# USF-IEEE-CS.net
KiCad netlist of a schematic drawn in Altium Designer
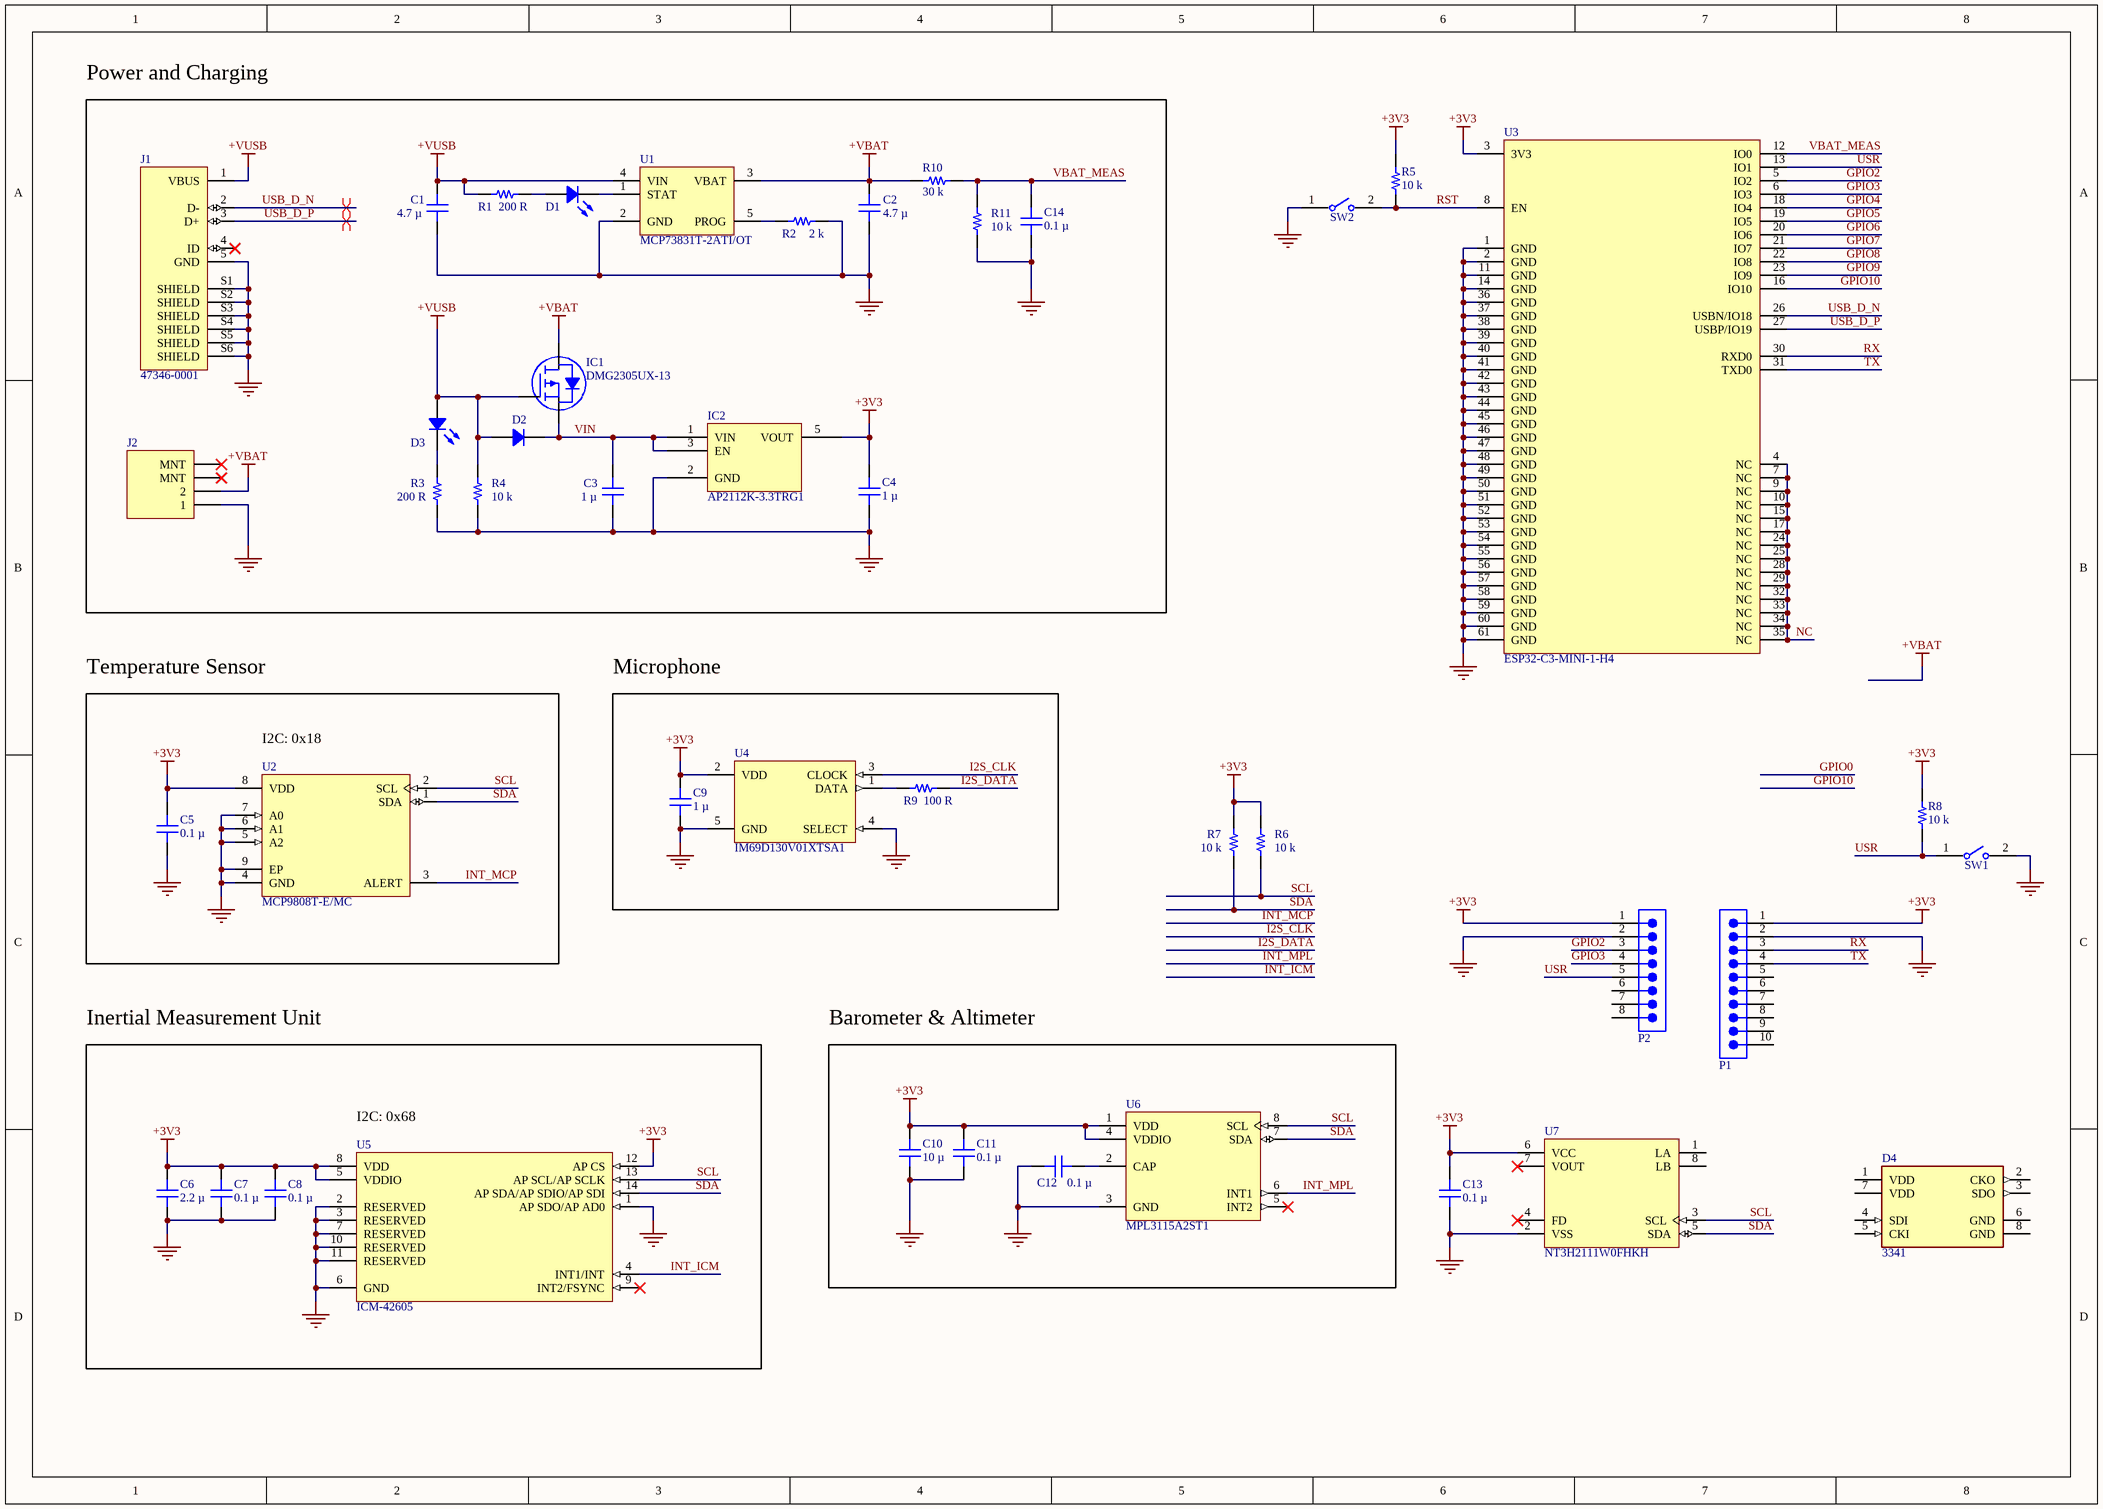
[diagram p0: USF-IEEE-CS.SchDoc]

(export (version "E")
  (design (tool "Eeschema 10.0.6"))
  (components
    (comp (ref "C1")
      (value "4.7 µF")
      (footprint "CAP 0402_1005")
      (description "CAP CER 4.7UF 10V X5R 0402")
      (fields
        (field (name "PART NUMBER") "CL05A475KP5NRNC")
        (field (name "CAPACITANCE") "4.7 µ")
        (field (name "MANUFACTURER") "Samsung Electro-Mechanics")
      )
      (libsource (lib "Celestial Altium Library - altium_library") (part "Capacitor"))
    )
    (comp (ref "C2")
      (value "4.7 µF")
      (footprint "CAP 0402_1005")
      (description "CAP CER 4.7UF 10V X5R 0402")
      (fields
        (field (name "PART NUMBER") "CL05A475KP5NRNC")
        (field (name "CAPACITANCE") "4.7 µ")
        (field (name "MANUFACTURER") "Samsung Electro-Mechanics")
      )
      (libsource (lib "Celestial Altium Library - altium_library") (part "Capacitor"))
    )
    (comp (ref "C3")
      (value "1 µ")
      (footprint "CAP 0402_1005")
      (description "CAP CER 1UF 10V X5R 0402")
      (fields (field (name "PART NUMBER") "885012105012") (field (name "MANUFACTURER") "Würth Elektronik"))
      (libsource (lib "Celestial Altium Library - altium_library") (part "Capacitor"))
    )
    (comp (ref "C4")
      (value "1 µ")
      (footprint "CAP 0402_1005")
      (description "CAP CER 1UF 10V X5R 0402")
      (fields (field (name "PART NUMBER") "885012105012") (field (name "MANUFACTURER") "Würth Elektronik"))
      (libsource (lib "Celestial Altium Library - altium_library") (part "Capacitor"))
    )
    (comp (ref "C5")
      (value "0.1 µF")
      (footprint "CAP 0402_1005")
      (description "CAP CER 0.1UF 50V X5R 0402")
      (fields
        (field (name "PART NUMBER") "CGA2B3X5R1H104M050BB")
        (field (name "CAPACITANCE") "0.1 µ")
        (field (name "MANUFACTURER") "TDK Corporation")
      )
      (libsource (lib "Celestial Altium Library - altium_library") (part "Capacitor"))
    )
    (comp (ref "C6")
      (value "2.2 µF")
      (footprint "CAP 0402_1005")
      (description "CAP CER 2.2UF 25V X5R 0402")
      (fields
        (field (name "PART NUMBER") "TMK105CBJ225KV-F")
        (field (name "CAPACITANCE") "2.2 µ")
        (field (name "MANUFACTURER") "Taiyo Yuden")
      )
      (libsource (lib "Celestial Altium Library - altium_library") (part "Capacitor"))
    )
    (comp (ref "C7")
      (value "0.1 µF")
      (footprint "CAP 0402_1005")
      (description "CAP CER 0.1UF 50V X5R 0402")
      (fields
        (field (name "PART NUMBER") "CGA2B3X5R1H104M050BB")
        (field (name "CAPACITANCE") "0.1 µ")
        (field (name "MANUFACTURER") "TDK Corporation")
      )
      (libsource (lib "Celestial Altium Library - altium_library") (part "Capacitor"))
    )
    (comp (ref "C8")
      (value "0.1 µF")
      (footprint "CAP 0402_1005")
      (description "CAP CER 0.1UF 50V X5R 0402")
      (fields
        (field (name "PART NUMBER") "CGA2B3X5R1H104M050BB")
        (field (name "CAPACITANCE") "0.1 µ")
        (field (name "MANUFACTURER") "TDK Corporation")
      )
      (libsource (lib "Celestial Altium Library - altium_library") (part "Capacitor"))
    )
    (comp (ref "C9")
      (value "1 µ")
      (footprint "CAP 0402_1005")
      (description "CAP CER 1UF 10V X5R 0402")
      (fields (field (name "PART NUMBER") "885012105012") (field (name "MANUFACTURER") "Würth Elektronik"))
      (libsource (lib "Celestial Altium Library - altium_library") (part "Capacitor"))
    )
    (comp (ref "C10")
      (value "10 µF")
      (footprint "CAP 0603_1608")
      (description "CAP CER 10UF 16V X5R 0603")
      (fields
        (field (name "PART NUMBER") "GRT188R61C106ME13D")
        (field (name "CAPACITANCE") "10 µ")
        (field (name "MANUFACTURER") "Murata Electronics")
      )
      (libsource (lib "Celestial Altium Library - altium_library") (part "Capacitor"))
    )
    (comp (ref "C11")
      (value "0.1 µF")
      (footprint "CAP 0402_1005")
      (description "CAP CER 0.1UF 50V X5R 0402")
      (fields
        (field (name "PART NUMBER") "CGA2B3X5R1H104M050BB")
        (field (name "CAPACITANCE") "0.1 µ")
        (field (name "MANUFACTURER") "TDK Corporation")
      )
      (libsource (lib "Celestial Altium Library - altium_library") (part "Capacitor"))
    )
    (comp (ref "C12")
      (value "0.1 µF")
      (footprint "CAP 0402_1005")
      (description "CAP CER 0.1UF 50V X5R 0402")
      (fields
        (field (name "PART NUMBER") "CGA2B3X5R1H104M050BB")
        (field (name "CAPACITANCE") "0.1 µ")
        (field (name "MANUFACTURER") "TDK Corporation")
      )
      (libsource (lib "Celestial Altium Library - altium_library") (part "Capacitor"))
    )
    (comp (ref "C13")
      (value "0.1 µF")
      (footprint "CAP 0402_1005")
      (description "CAP CER 0.1UF 50V X5R 0402")
      (fields
        (field (name "PART NUMBER") "CGA2B3X5R1H104M050BB")
        (field (name "CAPACITANCE") "0.1 µ")
        (field (name "MANUFACTURER") "TDK Corporation")
      )
      (libsource (lib "Celestial Altium Library - altium_library") (part "Capacitor"))
    )
    (comp (ref "C14")
      (value "0.1 µF")
      (footprint "CAP 0402_1005")
      (description "CAP CER 0.1UF 50V X5R 0402")
      (fields
        (field (name "PART NUMBER") "CGA2B3X5R1H104M050BB")
        (field (name "CAPACITANCE") "0.1 µ")
        (field (name "MANUFACTURER") "TDK Corporation")
      )
      (libsource (lib "Celestial Altium Library - altium_library") (part "Capacitor"))
    )
    (comp (ref "D1")
      (value "Red")
      (footprint "LED 0603_1608 RED")
      (description "LED RED CLEAR CHIP SMD")
      (fields (field (name "PART NUMBER") "XZMDK53W-8ST") (field (name "MANUFACTURER") "SunLED"))
      (libsource (lib "Celestial Altium Library - altium_library") (part "LED"))
    )
    (comp (ref "D2")
      (value "MBR120ESFT1G")
      (footprint "SOD123F")
      (description "DIODE SCHOTTKY 20V 1A SOD123L")
      (fields (field (name "MANUFACTURER") "ON Semiconductor"))
      (libsource (lib "Celestial Altium Library - altium_library") (part "Diode"))
    )
    (comp (ref "D3")
      (value "Blue")
      (footprint "LED 0603_1608 BLUE")
      (description "LED BLUE CLEAR CHIP SMD")
      (fields (field (name "PART NUMBER") "LTST-C193TBKT-5A") (field (name "MANUFACTURER") "Lite-On Inc."))
      (libsource (lib "Celestial Altium Library - altium_library") (part "LED"))
    )
    (comp (ref "D4")
      (value "3341")
      (footprint "FP-3341-MFG")
      (description "DotStar Micro LEDs (APA102-2020) - Smart SMD RGB LED - 10 Pack")
      (libsource (lib "University of South Florida") (part "81e4e4db83d5733156a58f1ba75e068"))
    )
    (comp (ref "IC1")
      (value "DMG2305UX-13")
      (footprint "DIODES SOT-23-3")
      (description "MOSFET P-CH 20V 4.2A SOT23")
      (fields (field (name "MANUFACTURER") "Diodes Incorporated"))
      (libsource (lib "Celestial Altium Library - altium_library") (part "DIODES MOSFET P-CH SOT-23-3"))
    )
    (comp (ref "IC2")
      (value "AP2112K-3.3TRG1")
      (footprint "DIODES SOT-23-5 W5")
      (description "IC REG LINEAR 3.3V 600MA SOT25")
      (fields (field (name "MANUFACTURER") "Diodes Incorporated"))
      (libsource (lib "Celestial Altium Library - altium_library") (part "DIODES INC AP2112K"))
    )
    (comp (ref "J1")
      (value "47346-0001")
      (footprint "MOLEX_47346-0001")
      (description "USB - micro B USB 2.0 Receptacle Connector 5 Position Surface Mount, Right Angle")
      (fields (field (name "MF") "Molex"))
      (libsource (lib "University of South Florida") (part "47346-0001"))
    )
    (comp (ref "J2")
      (value "SM02B-GHS-TB(LF)(SN)")
      (footprint "FP-SM02B-GHS-TB_LF_SN-MFG")
      (description "MCU 32-bit LPC1800 ARM Cortex M3 RISC 768KB Flash 3.3V 100-Pin TFBGA Tray")
      (libsource (lib "University of South Florida") (part "SM02B-GHS-TB"))
    )
    (comp (ref "P1")
      (value "61301011121")
      (footprint "61301011121")
      (description "WR-PHD Pin Header, THT, Vertical, pitch 2.54mm, 1 Row, 10P")
      (fields (field (name "MANUFACTURER") "Wurth Elektronik"))
      (libsource (lib "University of South Florida") (part "62001011121"))
    )
    (comp (ref "P2")
      (value "61300811121")
      (footprint "61300811121")
      (description "WR-PHD Pin Header, THT, Vertical, pitch 2.54mm, 1 Row, 8P")
      (fields (field (name "MANUFACTURER") "Wurth Elektronik"))
      (libsource (lib "University of South Florida") (part "62000811121"))
    )
    (comp (ref "R1")
      (value "200 R")
      (footprint "RES 0402_1005")
      (description "RES SMD 200 OHM 0.1% 1/16W 0402")
      (fields
        (field (name "PART NUMBER") "RN73C1E200RBTD")
        (field (name "MANUFACTURER") "TE Connectivity Passive Product")
      )
      (libsource (lib "Celestial Altium Library - altium_library") (part "Resistor"))
    )
    (comp (ref "R2")
      (value "2 k")
      (footprint "RES 0402_1005")
      (description "RES SMD 2K OHM 0.5% 1/16W 0402")
      (fields (field (name "PART NUMBER") "RR0510P-202-D") (field (name "MANUFACTURER") "Susumu"))
      (libsource (lib "Celestial Altium Library - altium_library") (part "Resistor"))
    )
    (comp (ref "R3")
      (value "200 R")
      (footprint "RES 0402_1005")
      (description "RES SMD 200 OHM 0.1% 1/16W 0402")
      (fields
        (field (name "PART NUMBER") "RN73C1E200RBTD")
        (field (name "MANUFACTURER") "TE Connectivity Passive Product")
      )
      (libsource (lib "Celestial Altium Library - altium_library") (part "Resistor"))
    )
    (comp (ref "R4")
      (value "10 k")
      (footprint "RES 0402_1005")
      (description "RES 10K OHM 0.1% 1/10W 0402")
      (fields
        (field (name "PART NUMBER") "RP73PF1E10KBTD")
        (field (name "MANUFACTURER") "TE Connectivity Passive Product")
      )
      (libsource (lib "Celestial Altium Library - altium_library") (part "Resistor"))
    )
    (comp (ref "R5")
      (value "10 k")
      (footprint "RES 0402_1005")
      (description "RES 10K OHM 0.1% 1/10W 0402")
      (fields
        (field (name "PART NUMBER") "RP73PF1E10KBTD")
        (field (name "MANUFACTURER") "TE Connectivity Passive Product")
      )
      (libsource (lib "Celestial Altium Library - altium_library") (part "Resistor"))
    )
    (comp (ref "R6")
      (value "10 k")
      (footprint "RES 0402_1005")
      (description "RES 10K OHM 0.1% 1/10W 0402")
      (fields
        (field (name "PART NUMBER") "RP73PF1E10KBTD")
        (field (name "MANUFACTURER") "TE Connectivity Passive Product")
      )
      (libsource (lib "Celestial Altium Library - altium_library") (part "Resistor"))
    )
    (comp (ref "R7")
      (value "10 k")
      (footprint "RES 0402_1005")
      (description "RES 10K OHM 0.1% 1/10W 0402")
      (fields
        (field (name "PART NUMBER") "RP73PF1E10KBTD")
        (field (name "MANUFACTURER") "TE Connectivity Passive Product")
      )
      (libsource (lib "Celestial Altium Library - altium_library") (part "Resistor"))
    )
    (comp (ref "R8")
      (value "10 k")
      (footprint "RES 0402_1005")
      (description "RES 10K OHM 0.1% 1/10W 0402")
      (fields
        (field (name "PART NUMBER") "RP73PF1E10KBTD")
        (field (name "MANUFACTURER") "TE Connectivity Passive Product")
      )
      (libsource (lib "Celestial Altium Library - altium_library") (part "Resistor"))
    )
    (comp (ref "R9")
      (value "100 R")
      (footprint "RES 0402_1005")
      (description "RESA-AS 0402 100R 5% 63MW TC200")
      (fields (field (name "PART NUMBER") "CR0402AJW-101GAS") (field (name "MANUFACTURER") "Bourns Inc."))
      (libsource (lib "Celestial Altium Library - altium_library") (part "Resistor"))
    )
    (comp (ref "R10")
      (value "30 k")
      (footprint "RES 0402_1005")
      (description "RES SMD 30K OHM 0.1% 1/16W 0402")
      (fields
        (field (name "PART NUMBER") "CPF0402B30KE1")
        (field (name "MANUFACTURER") "TE Connectivity Passive Product")
      )
      (libsource (lib "Celestial Altium Library - altium_library") (part "Resistor"))
    )
    (comp (ref "R11")
      (value "10 k")
      (footprint "RES 0402_1005")
      (description "RES 10K OHM 0.1% 1/10W 0402")
      (fields
        (field (name "PART NUMBER") "RP73PF1E10KBTD")
        (field (name "MANUFACTURER") "TE Connectivity Passive Product")
      )
      (libsource (lib "Celestial Altium Library - altium_library") (part "Resistor"))
    )
    (comp (ref "SW1")
      (value "B3U-1000P")
      (footprint "FP-B3U-1000P-MFG")
      (libsource (lib "University of South Florida") (part "ae622034201233ca1abcedc05908f33"))
    )
    (comp (ref "SW2")
      (value "B3U-1000P")
      (footprint "FP-B3U-1000P-MFG")
      (libsource (lib "University of South Florida") (part "ae622034201233ca1abcedc05908f33"))
    )
    (comp (ref "U1")
      (value "MCP73831T-2ATI/OT")
      (footprint "FP-C04-091-OT-MFG")
      (description "Power Supply Support Circuit, Adjustable, 1 Channel, 3.45, PDSO5")
      (libsource (lib "University of South Florida") (part "MCP73831T-2ATI/OT"))
    )
    (comp (ref "U2")
      (value "MCP9808T-E/MC")
      (footprint "MCHP-DFN-MC8_V")
      (description "Serial Switch/Digital Sensor, 16 Bit(s), 1Cel, Rectangular, 8 Pin, Surface Mount")
      (libsource (lib "University of South Florida") (part "MCHP-MCP9808-DFN-8"))
    )
    (comp (ref "U3")
      (value "ESP32-C3-MINI-1-H4")
      (footprint "ESP32C3MINI1H4")
      (libsource (lib "University of South Florida") (part "ESP32-C3-MINI-1-H4"))
    )
    (comp (ref "U4")
      (value "IM69D130V01XTSA1")
      (footprint "FP-PG-LLGA-5-MFG")
      (description "Consumer Circuit, PBGA5")
      (libsource (lib "University of South Florida") (part "IM69D130V01XTSA1"))
    )
    (comp (ref "U5")
      (value "ICM-42605")
      (footprint "FP-ICM-42605-MFG")
      (description "Open-drain, CMOS, 14 Pin")
      (libsource (lib "University of South Florida") (part "ICM-42605"))
    )
    (comp (ref "U6")
      (value "MPL3115A2ST1")
      (footprint "FRES-2153-01_V")
      (description "Piezoresistive Sensor, Absolute, 2.9Psi Min, 15.9Psi Max, 0.1-0.9V, Rectangular, Surface Mount")
      (libsource (lib "University of South Florida") (part "FRES-MPL3115A2-8"))
    )
    (comp (ref "U7")
      (value "NT3H2111W0FHKH")
      (footprint "NT3H2111W0FHKH-FP")
      (description "RFID Transponder IC 13.56MHz ISO 14443 I2C 3.3V 8-XFQFN Exposed Pad")
      (libsource (lib "University of South Florida") (part "NT3H2111W0FHKH"))
    )
  )
  (nets
    (net (code "1") (name "+3V3") (class "Default")
      (node (ref "C10") (pin "2") (pinfunction "2_2") (pintype "passive"))
      (node (ref "C11") (pin "2") (pinfunction "2_2") (pintype "passive"))
      (node (ref "C13") (pin "2") (pinfunction "2_2") (pintype "passive"))
      (node (ref "C4") (pin "2") (pinfunction "2_2") (pintype "passive"))
      (node (ref "C5") (pin "2") (pinfunction "2_2") (pintype "passive"))
      (node (ref "C6") (pin "2") (pinfunction "2_2") (pintype "passive"))
      (node (ref "C7") (pin "2") (pinfunction "2_2") (pintype "passive"))
      (node (ref "C8") (pin "2") (pinfunction "2_2") (pintype "passive"))
      (node (ref "C9") (pin "2") (pinfunction "2_2") (pintype "passive"))
      (node (ref "IC2") (pin "5") (pinfunction "VOUT_5") (pintype "passive"))
      (node (ref "P1") (pin "1") (pinfunction "1_1") (pintype "passive"))
      (node (ref "P2") (pin "1") (pinfunction "1_1") (pintype "passive"))
      (node (ref "R5") (pin "2") (pinfunction "2_2") (pintype "passive"))
      (node (ref "R6") (pin "2") (pinfunction "2_2") (pintype "passive"))
      (node (ref "R7") (pin "2") (pinfunction "2_2") (pintype "passive"))
      (node (ref "R8") (pin "2") (pinfunction "2_2") (pintype "passive"))
      (node (ref "U2") (pin "8") (pinfunction "VDD_8") (pintype "power_in"))
      (node (ref "U3") (pin "3") (pinfunction "3V3_3") (pintype "passive"))
      (node (ref "U4") (pin "2") (pinfunction "VDD_2") (pintype "power_in"))
      (node (ref "U5") (pin "12") (pinfunction "AP_CS_12") (pintype "input"))
      (node (ref "U5") (pin "5") (pinfunction "VDDIO_5") (pintype "power_in"))
      (node (ref "U5") (pin "8") (pinfunction "VDD_8") (pintype "power_in"))
      (node (ref "U6") (pin "1") (pinfunction "VDD_1") (pintype "power_in"))
      (node (ref "U6") (pin "4") (pinfunction "VDDIO_4") (pintype "power_in"))
      (node (ref "U7") (pin "6") (pinfunction "VCC_6") (pintype "power_in"))
    )
    (net (code "2") (name "+VBAT") (class "Default")
      (node (ref "C2") (pin "2") (pinfunction "2_2") (pintype "passive"))
      (node (ref "IC1") (pin "3") (pinfunction "D_3") (pintype "passive"))
      (node (ref "J2") (pin "2") (pinfunction "2_2") (pintype "passive"))
      (node (ref "R10") (pin "2") (pinfunction "2_2") (pintype "passive"))
      (node (ref "U1") (pin "3") (pinfunction "VBAT_3") (pintype "power_in"))
    )
    (net (code "3") (name "+VUSB") (class "Default")
      (node (ref "C1") (pin "2") (pinfunction "2_2") (pintype "passive"))
      (node (ref "D2") (pin "1") (pinfunction "1_1") (pintype "passive"))
      (node (ref "D3") (pin "1") (pinfunction "1_1") (pintype "passive"))
      (node (ref "IC1") (pin "1") (pinfunction "G_1") (pintype "passive"))
      (node (ref "J1") (pin "1") (pinfunction "VBUS_1") (pintype "power_in"))
      (node (ref "R1") (pin "2") (pinfunction "2_2") (pintype "passive"))
      (node (ref "R4") (pin "1") (pinfunction "1_1") (pintype "passive"))
      (node (ref "U1") (pin "4") (pinfunction "VIN_4") (pintype "power_in"))
    )
    (net (code "5") (name "/GPIO2") (class "Default")
      (node (ref "P2") (pin "3") (pinfunction "3_3") (pintype "passive"))
      (node (ref "U3") (pin "5") (pinfunction "IO2_5") (pintype "passive"))
    )
    (net (code "6") (name "/GPIO3") (class "Default")
      (node (ref "P2") (pin "4") (pinfunction "4_4") (pintype "passive"))
      (node (ref "U3") (pin "6") (pinfunction "IO3_6") (pintype "passive"))
    )
    (net (code "7") (name "/GPIO4") (class "Default")
      (node (ref "U3") (pin "18") (pinfunction "IO4_18") (pintype "passive"))
    )
    (net (code "8") (name "/GPIO5") (class "Default")
      (node (ref "U3") (pin "19") (pinfunction "IO5_19") (pintype "passive"))
    )
    (net (code "9") (name "/GPIO6") (class "Default")
      (node (ref "U3") (pin "20") (pinfunction "IO6_20") (pintype "passive"))
    )
    (net (code "10") (name "/GPIO7") (class "Default")
      (node (ref "U3") (pin "21") (pinfunction "IO7_21") (pintype "passive"))
    )
    (net (code "11") (name "/GPIO8") (class "Default")
      (node (ref "U3") (pin "22") (pinfunction "IO8_22") (pintype "passive"))
    )
    (net (code "12") (name "/GPIO9") (class "Default")
      (node (ref "U3") (pin "23") (pinfunction "IO9_23") (pintype "passive"))
    )
    (net (code "13") (name "/GPIO10") (class "Default")
      (node (ref "U3") (pin "16") (pinfunction "IO10_16") (pintype "passive"))
    )
    (net (code "14") (name "/I2S_CLK") (class "Default")
      (node (ref "U4") (pin "3") (pinfunction "CLOCK_3") (pintype "input"))
    )
    (net (code "15") (name "/I2S_DATA") (class "Default")
      (node (ref "R9") (pin "2") (pinfunction "2_2") (pintype "passive"))
    )
    (net (code "16") (name "/INT_ICM") (class "Default")
      (node (ref "U5") (pin "4") (pinfunction "INT1/INT_4") (pintype "input"))
    )
    (net (code "17") (name "/INT_MCP") (class "Default")
      (node (ref "U2") (pin "3") (pinfunction "ALERT_3") (pintype "open_collector"))
    )
    (net (code "18") (name "/INT_MPL") (class "Default")
      (node (ref "U6") (pin "6") (pinfunction "INT1_6") (pintype "output"))
    )
    (net (code "19") (name "/NC") (class "Default")
      (node (ref "U3") (pin "10") (pinfunction "NC_10") (pintype "passive"))
      (node (ref "U3") (pin "15") (pinfunction "NC_15") (pintype "passive"))
      (node (ref "U3") (pin "17") (pinfunction "NC_17") (pintype "passive"))
      (node (ref "U3") (pin "24") (pinfunction "NC_24") (pintype "passive"))
      (node (ref "U3") (pin "25") (pinfunction "NC_25") (pintype "passive"))
      (node (ref "U3") (pin "28") (pinfunction "NC_28") (pintype "passive"))
      (node (ref "U3") (pin "29") (pinfunction "NC_29") (pintype "passive"))
      (node (ref "U3") (pin "32") (pinfunction "NC_32") (pintype "passive"))
      (node (ref "U3") (pin "33") (pinfunction "NC_33") (pintype "passive"))
      (node (ref "U3") (pin "34") (pinfunction "NC_34") (pintype "passive"))
      (node (ref "U3") (pin "35") (pinfunction "NC_35") (pintype "passive"))
      (node (ref "U3") (pin "4") (pinfunction "NC_4") (pintype "passive"))
      (node (ref "U3") (pin "7") (pinfunction "NC_7") (pintype "passive"))
      (node (ref "U3") (pin "9") (pinfunction "NC_9") (pintype "passive"))
    )
    (net (code "20") (name "/RST") (class "Default")
      (node (ref "R5") (pin "1") (pinfunction "1_1") (pintype "passive"))
      (node (ref "SW2") (pin "2") (pinfunction "2_2") (pintype "passive"))
      (node (ref "U3") (pin "8") (pinfunction "EN_8") (pintype "passive"))
    )
    (net (code "21") (name "/RX") (class "Default")
      (node (ref "P1") (pin "3") (pinfunction "3_3") (pintype "passive"))
      (node (ref "U3") (pin "30") (pinfunction "RXD0_30") (pintype "passive"))
    )
    (net (code "22") (name "/SCL") (class "Default")
      (node (ref "R6") (pin "1") (pinfunction "1_1") (pintype "passive"))
      (node (ref "U2") (pin "2") (pinfunction "SCL_2") (pintype "input"))
      (node (ref "U5") (pin "13") (pinfunction "AP_SCL/AP_SCLK_13") (pintype "input"))
      (node (ref "U6") (pin "8") (pinfunction "SCL_8") (pintype "input"))
      (node (ref "U7") (pin "3") (pinfunction "SCL_3") (pintype "input"))
    )
    (net (code "23") (name "/SDA") (class "Default")
      (node (ref "R7") (pin "1") (pinfunction "1_1") (pintype "passive"))
      (node (ref "U2") (pin "1") (pinfunction "SDA_1") (pintype "bidirectional"))
      (node (ref "U5") (pin "14") (pinfunction "AP_SDA/AP_SDIO/AP_SDI_14") (pintype "input"))
      (node (ref "U6") (pin "7") (pinfunction "SDA_7") (pintype "bidirectional"))
      (node (ref "U7") (pin "5") (pinfunction "SDA_5") (pintype "bidirectional"))
    )
    (net (code "24") (name "/TX") (class "Default")
      (node (ref "P1") (pin "4") (pinfunction "4_4") (pintype "passive"))
      (node (ref "U3") (pin "31") (pinfunction "TXD0_31") (pintype "passive"))
    )
    (net (code "25") (name "/USB_D_N") (class "Default")
      (node (ref "J1") (pin "2") (pinfunction "D-_2") (pintype "bidirectional"))
      (node (ref "U3") (pin "26") (pinfunction "USBN/IO18_26") (pintype "passive"))
    )
    (net (code "26") (name "/USB_D_P") (class "Default")
      (node (ref "J1") (pin "3") (pinfunction "D+_3") (pintype "bidirectional"))
      (node (ref "U3") (pin "27") (pinfunction "USBP/IO19_27") (pintype "passive"))
    )
    (net (code "27") (name "/USR") (class "Default")
      (node (ref "P2") (pin "5") (pinfunction "5_5") (pintype "passive"))
      (node (ref "R8") (pin "1") (pinfunction "1_1") (pintype "passive"))
      (node (ref "SW1") (pin "1") (pinfunction "1_1") (pintype "passive"))
      (node (ref "U3") (pin "13") (pinfunction "IO1_13") (pintype "passive"))
    )
    (net (code "28") (name "/VBAT_MEAS") (class "Default")
      (node (ref "C14") (pin "2") (pinfunction "2_2") (pintype "passive"))
      (node (ref "R10") (pin "1") (pinfunction "1_1") (pintype "passive"))
      (node (ref "R11") (pin "2") (pinfunction "2_2") (pintype "passive"))
      (node (ref "U3") (pin "12") (pinfunction "IO0_12") (pintype "passive"))
    )
    (net (code "29") (name "/VIN") (class "Default")
      (node (ref "C3") (pin "2") (pinfunction "2_2") (pintype "passive"))
      (node (ref "D2") (pin "2") (pinfunction "2_2") (pintype "passive"))
      (node (ref "IC1") (pin "2") (pinfunction "S_2") (pintype "passive"))
      (node (ref "IC2") (pin "1") (pinfunction "VIN_1") (pintype "passive"))
      (node (ref "IC2") (pin "3") (pinfunction "EN_3") (pintype "passive"))
    )
    (net (code "30") (name "GND") (class "Default")
      (node (ref "C1") (pin "1") (pinfunction "1_1") (pintype "passive"))
      (node (ref "C10") (pin "1") (pinfunction "1_1") (pintype "passive"))
      (node (ref "C11") (pin "1") (pinfunction "1_1") (pintype "passive"))
      (node (ref "C12") (pin "2") (pinfunction "2_2") (pintype "passive"))
      (node (ref "C13") (pin "1") (pinfunction "1_1") (pintype "passive"))
      (node (ref "C14") (pin "1") (pinfunction "1_1") (pintype "passive"))
      (node (ref "C2") (pin "1") (pinfunction "1_1") (pintype "passive"))
      (node (ref "C3") (pin "1") (pinfunction "1_1") (pintype "passive"))
      (node (ref "C4") (pin "1") (pinfunction "1_1") (pintype "passive"))
      (node (ref "C5") (pin "1") (pinfunction "1_1") (pintype "passive"))
      (node (ref "C6") (pin "1") (pinfunction "1_1") (pintype "passive"))
      (node (ref "C7") (pin "1") (pinfunction "1_1") (pintype "passive"))
      (node (ref "C8") (pin "1") (pinfunction "1_1") (pintype "passive"))
      (node (ref "C9") (pin "1") (pinfunction "1_1") (pintype "passive"))
      (node (ref "IC2") (pin "2") (pinfunction "GND_2") (pintype "passive"))
      (node (ref "J1") (pin "5") (pinfunction "GND_5") (pintype "power_in"))
      (node (ref "J1") (pin "S1") (pinfunction "SHIELD_S1") (pintype "passive"))
      (node (ref "J1") (pin "S2") (pinfunction "SHIELD_S2") (pintype "passive"))
      (node (ref "J1") (pin "S3") (pinfunction "SHIELD_S3") (pintype "passive"))
      (node (ref "J1") (pin "S4") (pinfunction "SHIELD_S4") (pintype "passive"))
      (node (ref "J1") (pin "S5") (pinfunction "SHIELD_S5") (pintype "passive"))
      (node (ref "J1") (pin "S6") (pinfunction "SHIELD_S6") (pintype "passive"))
      (node (ref "J2") (pin "1") (pinfunction "1_1") (pintype "passive"))
      (node (ref "P1") (pin "2") (pinfunction "2_2") (pintype "passive"))
      (node (ref "P2") (pin "2") (pinfunction "2_2") (pintype "passive"))
      (node (ref "R11") (pin "1") (pinfunction "1_1") (pintype "passive"))
      (node (ref "R2") (pin "2") (pinfunction "2_2") (pintype "passive"))
      (node (ref "R3") (pin "1") (pinfunction "1_1") (pintype "passive"))
      (node (ref "R4") (pin "2") (pinfunction "2_2") (pintype "passive"))
      (node (ref "SW1") (pin "2") (pinfunction "2_2") (pintype "passive"))
      (node (ref "SW2") (pin "1") (pinfunction "1_1") (pintype "passive"))
      (node (ref "U1") (pin "2") (pinfunction "GND_2") (pintype "power_in"))
      (node (ref "U2") (pin "4") (pinfunction "GND_4") (pintype "power_in"))
      (node (ref "U2") (pin "5") (pinfunction "A2_5") (pintype "input"))
      (node (ref "U2") (pin "6") (pinfunction "A1_6") (pintype "input"))
      (node (ref "U2") (pin "7") (pinfunction "A0_7") (pintype "input"))
      (node (ref "U2") (pin "9") (pinfunction "EP_9") (pintype "power_in"))
      (node (ref "U3") (pin "1") (pinfunction "GND_1") (pintype "passive"))
      (node (ref "U3") (pin "11") (pinfunction "GND_11") (pintype "passive"))
      (node (ref "U3") (pin "14") (pinfunction "GND_14") (pintype "passive"))
      (node (ref "U3") (pin "2") (pinfunction "GND_2") (pintype "passive"))
      (node (ref "U3") (pin "36") (pinfunction "GND_36") (pintype "passive"))
      (node (ref "U3") (pin "37") (pinfunction "GND_37") (pintype "passive"))
      (node (ref "U3") (pin "38") (pinfunction "GND_38") (pintype "passive"))
      (node (ref "U3") (pin "39") (pinfunction "GND_39") (pintype "passive"))
      (node (ref "U3") (pin "40") (pinfunction "GND_40") (pintype "passive"))
      (node (ref "U3") (pin "41") (pinfunction "GND_41") (pintype "passive"))
      (node (ref "U3") (pin "42") (pinfunction "GND_42") (pintype "passive"))
      (node (ref "U3") (pin "43") (pinfunction "GND_43") (pintype "passive"))
      (node (ref "U3") (pin "44") (pinfunction "GND_44") (pintype "passive"))
      (node (ref "U3") (pin "45") (pinfunction "GND_45") (pintype "passive"))
      (node (ref "U3") (pin "46") (pinfunction "GND_46") (pintype "passive"))
      (node (ref "U3") (pin "47") (pinfunction "GND_47") (pintype "passive"))
      (node (ref "U3") (pin "48") (pinfunction "GND_48") (pintype "passive"))
      (node (ref "U3") (pin "49") (pinfunction "GND_49") (pintype "passive"))
      (node (ref "U3") (pin "50") (pinfunction "GND_50") (pintype "passive"))
      (node (ref "U3") (pin "51") (pinfunction "GND_51") (pintype "passive"))
      (node (ref "U3") (pin "52") (pinfunction "GND_52") (pintype "passive"))
      (node (ref "U3") (pin "53") (pinfunction "GND_53") (pintype "passive"))
      (node (ref "U3") (pin "54") (pinfunction "GND_54") (pintype "passive"))
      (node (ref "U3") (pin "55") (pinfunction "GND_55") (pintype "passive"))
      (node (ref "U3") (pin "56") (pinfunction "GND_56") (pintype "passive"))
      (node (ref "U3") (pin "57") (pinfunction "GND_57") (pintype "passive"))
      (node (ref "U3") (pin "58") (pinfunction "GND_58") (pintype "passive"))
      (node (ref "U3") (pin "59") (pinfunction "GND_59") (pintype "passive"))
      (node (ref "U3") (pin "60") (pinfunction "GND_60") (pintype "passive"))
      (node (ref "U3") (pin "61") (pinfunction "GND_61") (pintype "passive"))
      (node (ref "U4") (pin "4") (pinfunction "SELECT_4") (pintype "input"))
      (node (ref "U4") (pin "5") (pinfunction "GND_5") (pintype "power_in"))
      (node (ref "U5") (pin "1") (pinfunction "AP_SDO/AP_AD0_1") (pintype "input"))
      (node (ref "U5") (pin "10") (pinfunction "RESERVED_10") (pintype "passive"))
      (node (ref "U5") (pin "11") (pinfunction "RESERVED_11") (pintype "passive"))
      (node (ref "U5") (pin "2") (pinfunction "RESERVED_2") (pintype "passive"))
      (node (ref "U5") (pin "3") (pinfunction "RESERVED_3") (pintype "passive"))
      (node (ref "U5") (pin "6") (pinfunction "GND_6") (pintype "power_in"))
      (node (ref "U5") (pin "7") (pinfunction "RESERVED_7") (pintype "passive"))
      (node (ref "U6") (pin "3") (pinfunction "GND_3") (pintype "power_in"))
      (node (ref "U7") (pin "2") (pinfunction "VSS_2") (pintype "power_in"))
    )
    (net (code "31") (name "Net-(D1-Pad1)") (class "Default")
      (node (ref "D1") (pin "1") (pinfunction "1_1") (pintype "passive"))
      (node (ref "R1") (pin "1") (pinfunction "1_1") (pintype "passive"))
    )
    (net (code "32") (name "Net-(D3-Pad2)") (class "Default")
      (node (ref "D3") (pin "2") (pinfunction "2_2") (pintype "passive"))
      (node (ref "R3") (pin "2") (pinfunction "2_2") (pintype "passive"))
    )
    (net (code "33") (name "Net-(U1-PROG)") (class "Default")
      (node (ref "R2") (pin "1") (pinfunction "1_1") (pintype "passive"))
      (node (ref "U1") (pin "5") (pinfunction "PROG_5") (pintype "passive"))
    )
    (net (code "34") (name "Net-(U1-STAT)") (class "Default")
      (node (ref "D1") (pin "2") (pinfunction "2_2") (pintype "passive"))
      (node (ref "U1") (pin "1") (pinfunction "STAT_1") (pintype "passive"))
    )
    (net (code "35") (name "Net-(U4-DATA)") (class "Default")
      (node (ref "R9") (pin "1") (pinfunction "1_1") (pintype "passive"))
      (node (ref "U4") (pin "1") (pinfunction "DATA_1") (pintype "output"))
    )
    (net (code "36") (name "Net-(U6-CAP)") (class "Default")
      (node (ref "C12") (pin "1") (pinfunction "1_1") (pintype "passive"))
      (node (ref "U6") (pin "2") (pinfunction "CAP_2") (pintype "passive"))
    )
    (net (code "37") (name "unconnected-(D4-CKI-Pad5)") (class "Default")
      (node (ref "D4") (pin "5") (pinfunction "CKI_5") (pintype "input"))
    )
    (net (code "38") (name "unconnected-(D4-CKO-Pad2)") (class "Default")
      (node (ref "D4") (pin "2") (pinfunction "CKO_2") (pintype "output"))
    )
    (net (code "39") (name "unconnected-(D4-GND-Pad6)") (class "Default")
      (node (ref "D4") (pin "6") (pinfunction "GND_6") (pintype "power_in"))
    )
    (net (code "40") (name "unconnected-(D4-GND-Pad8)") (class "Default")
      (node (ref "D4") (pin "8") (pinfunction "GND_8") (pintype "power_in"))
    )
    (net (code "41") (name "unconnected-(D4-SDI-Pad4)") (class "Default")
      (node (ref "D4") (pin "4") (pinfunction "SDI_4") (pintype "input"))
    )
    (net (code "42") (name "unconnected-(D4-SDO-Pad3)") (class "Default")
      (node (ref "D4") (pin "3") (pinfunction "SDO_3") (pintype "output"))
    )
    (net (code "43") (name "unconnected-(D4-VDD-Pad1)") (class "Default")
      (node (ref "D4") (pin "1") (pinfunction "VDD_1") (pintype "power_in"))
    )
    (net (code "44") (name "unconnected-(D4-VDD-Pad7)") (class "Default")
      (node (ref "D4") (pin "7") (pinfunction "VDD_7") (pintype "power_in"))
    )
    (net (code "45") (name "unconnected-(J1-ID-Pad4)") (class "Default")
      (node (ref "J1") (pin "4") (pinfunction "ID_4") (pintype "bidirectional+no_connect"))
    )
    (net (code "46") (name "unconnected-(J2-MNT-Pad3)") (class "Default")
      (node (ref "J2") (pin "3") (pinfunction "MNT_3") (pintype "passive+no_connect"))
    )
    (net (code "47") (name "unconnected-(J2-MNT-Pad4)") (class "Default")
      (node (ref "J2") (pin "4") (pinfunction "MNT_4") (pintype "passive+no_connect"))
    )
    (net (code "48") (name "unconnected-(P1-Pad5)") (class "Default")
      (node (ref "P1") (pin "5") (pinfunction "5_5") (pintype "passive"))
    )
    (net (code "49") (name "unconnected-(P1-Pad6)") (class "Default")
      (node (ref "P1") (pin "6") (pinfunction "6_6") (pintype "passive"))
    )
    (net (code "50") (name "unconnected-(P1-Pad7)") (class "Default")
      (node (ref "P1") (pin "7") (pinfunction "7_7") (pintype "passive"))
    )
    (net (code "51") (name "unconnected-(P1-Pad8)") (class "Default")
      (node (ref "P1") (pin "8") (pinfunction "8_8") (pintype "passive"))
    )
    (net (code "52") (name "unconnected-(P1-Pad9)") (class "Default")
      (node (ref "P1") (pin "9") (pinfunction "9_9") (pintype "passive"))
    )
    (net (code "53") (name "unconnected-(P1-Pad10)") (class "Default")
      (node (ref "P1") (pin "10") (pinfunction "10_10") (pintype "passive"))
    )
    (net (code "54") (name "unconnected-(P2-Pad6)") (class "Default")
      (node (ref "P2") (pin "6") (pinfunction "6_6") (pintype "passive"))
    )
    (net (code "55") (name "unconnected-(P2-Pad7)") (class "Default")
      (node (ref "P2") (pin "7") (pinfunction "7_7") (pintype "passive"))
    )
    (net (code "56") (name "unconnected-(P2-Pad8)") (class "Default")
      (node (ref "P2") (pin "8") (pinfunction "8_8") (pintype "passive"))
    )
    (net (code "57") (name "unconnected-(U5-INT2{slash}FSYNC-Pad9)") (class "Default")
      (node (ref "U5") (pin "9") (pinfunction "INT2/FSYNC_9") (pintype "input+no_connect"))
    )
    (net (code "58") (name "unconnected-(U6-INT2-Pad5)") (class "Default")
      (node (ref "U6") (pin "5") (pinfunction "INT2_5") (pintype "output+no_connect"))
    )
    (net (code "59") (name "unconnected-(U7-FD-Pad4)") (class "Default")
      (node (ref "U7") (pin "4") (pinfunction "FD_4") (pintype "passive+no_connect"))
    )
    (net (code "60") (name "unconnected-(U7-LA-Pad1)") (class "Default")
      (node (ref "U7") (pin "1") (pinfunction "LA_1") (pintype "passive"))
    )
    (net (code "61") (name "unconnected-(U7-LB-Pad8)") (class "Default")
      (node (ref "U7") (pin "8") (pinfunction "LB_8") (pintype "passive"))
    )
    (net (code "62") (name "unconnected-(U7-VOUT-Pad7)") (class "Default")
      (node (ref "U7") (pin "7") (pinfunction "VOUT_7") (pintype "power_in+no_connect"))
    )
  )
)
